# nrfusb.net
KiCad netlist of a schematic drawn in EAGLE
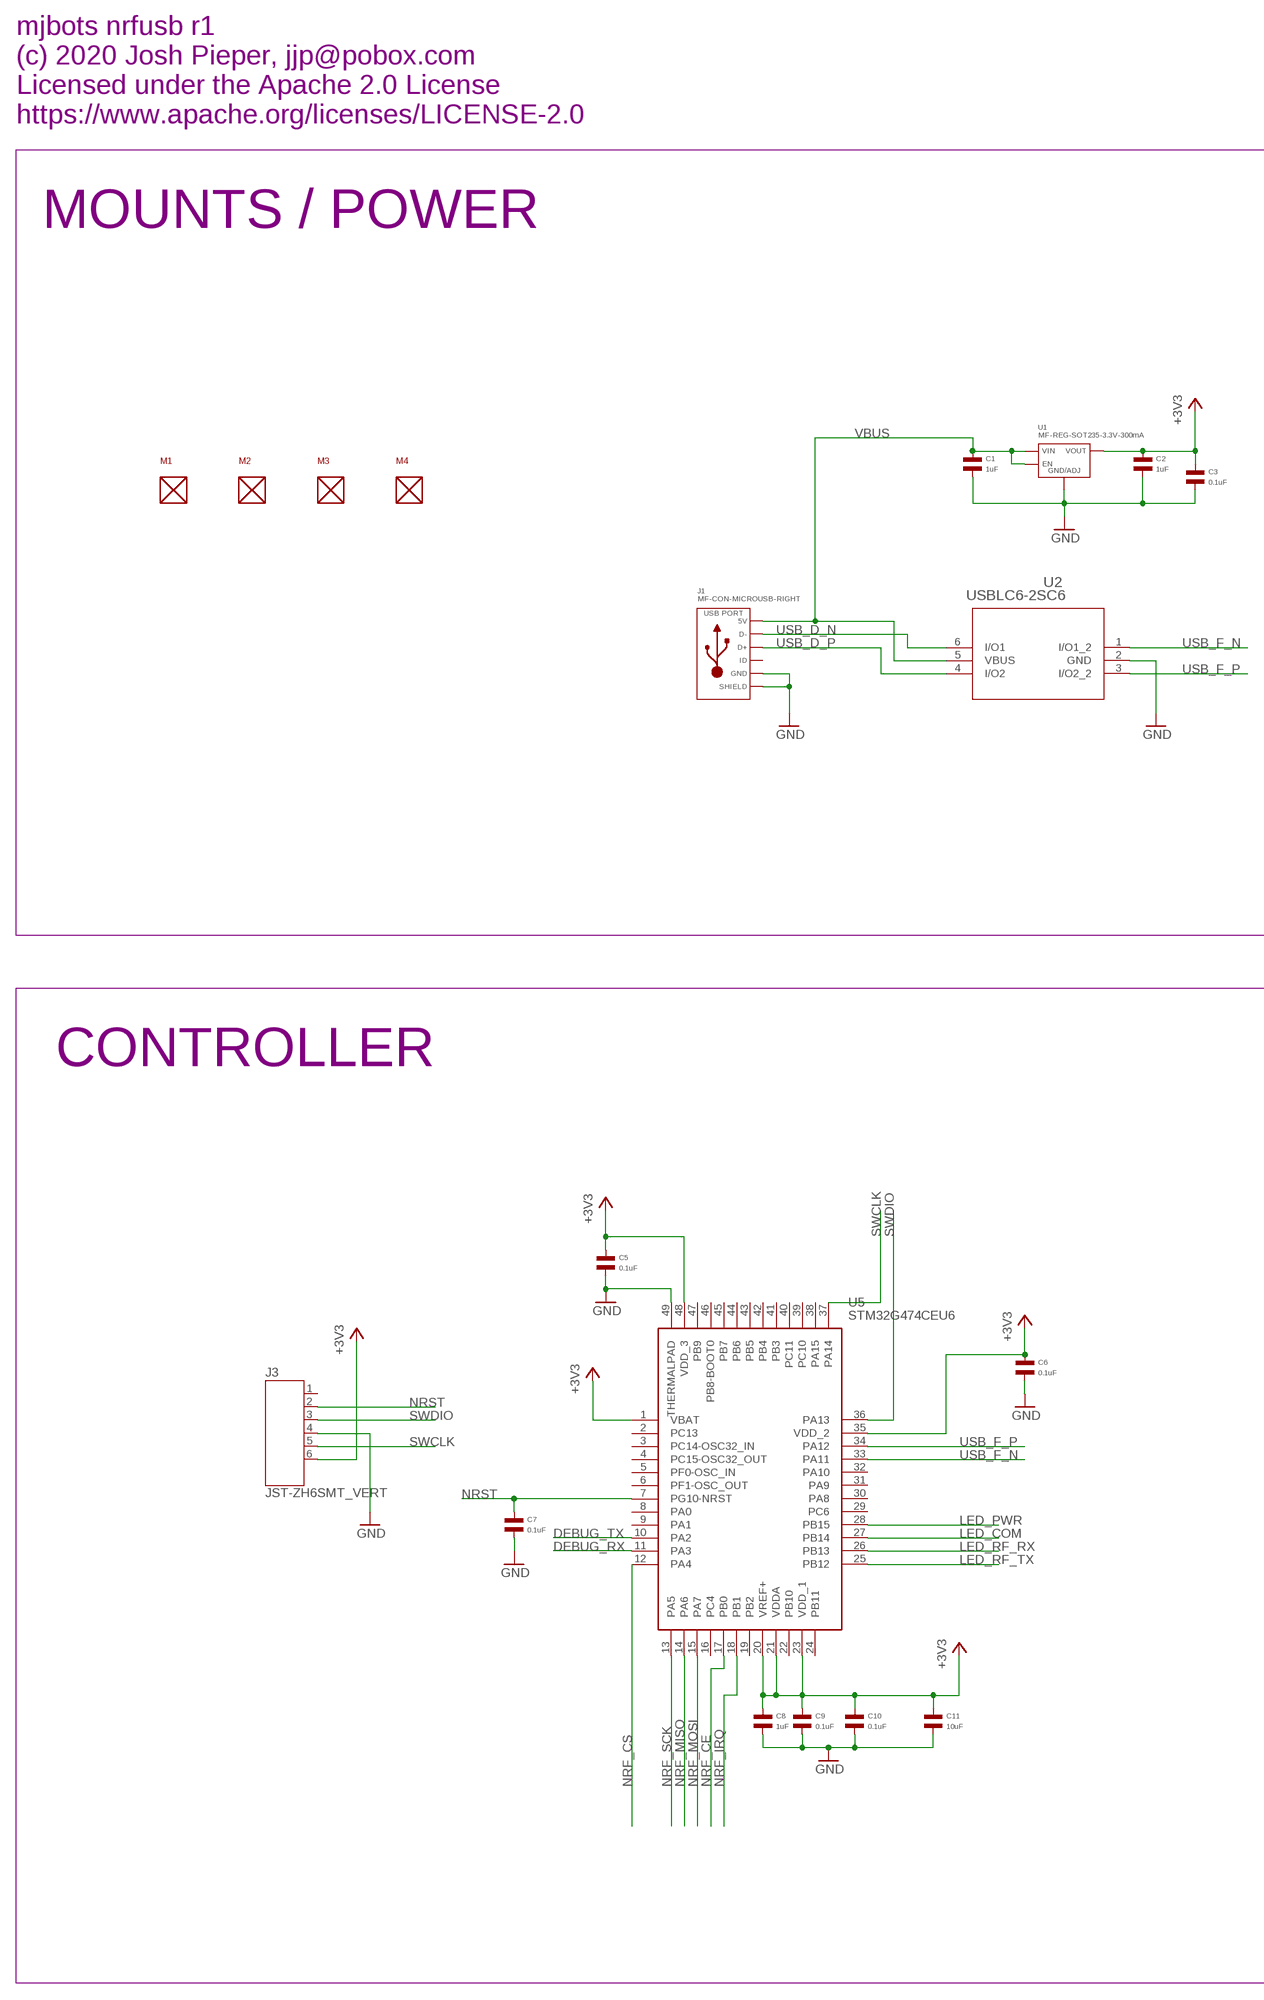
[diagram p0: schematic, sheet 1, part 1 of 2]
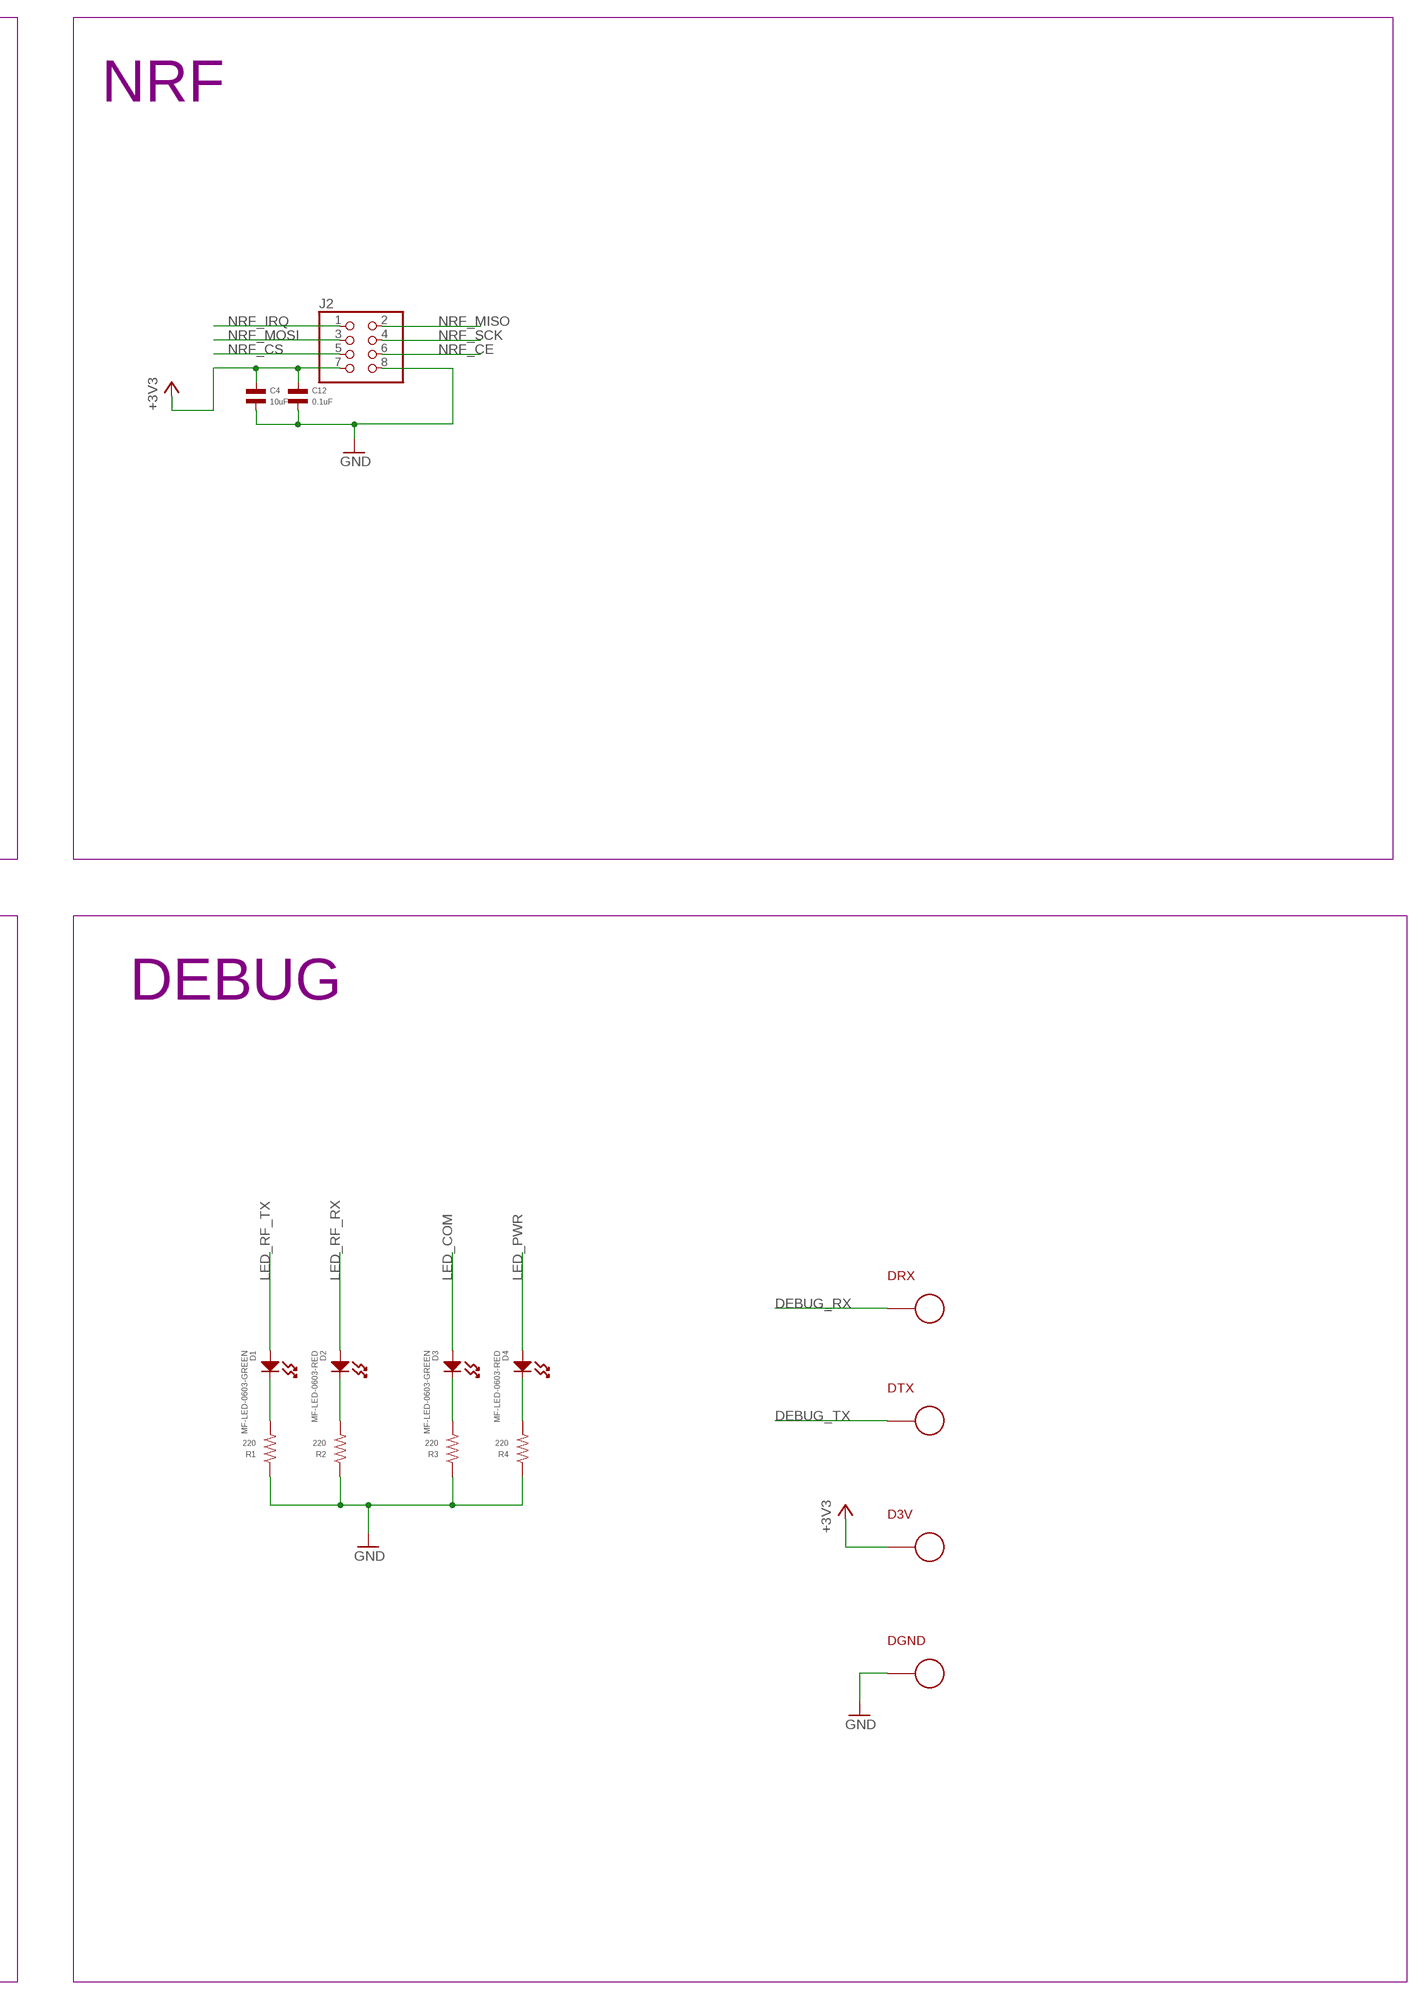
[diagram p1: schematic, sheet 1, part 2 of 2]

(export (version "E")
  (design (tool "Eeschema 10.0.6"))
  (components
    (comp (ref "C1")
      (value "1uF")
      (footprint "eagle-import:C0603")
      (fields (field (name "HOUSEPART") "YES") (field (name "MPN") "MF-CAP-0603-1uF"))
      (libsource (lib "eagle-import") (part "CAPACITOR_NP_0603"))
    )
    (comp (ref "C2")
      (value "1uF")
      (footprint "eagle-import:C0603")
      (fields (field (name "HOUSEPART") "YES") (field (name "MPN") "MF-CAP-0603-1uF"))
      (libsource (lib "eagle-import") (part "CAPACITOR_NP_0603"))
    )
    (comp (ref "C3")
      (value "0.1uF")
      (footprint "eagle-import:C0402")
      (fields (field (name "HOUSEPART") "YES") (field (name "MPN") "MF-CAP-0402-0.1uF"))
      (libsource (lib "eagle-import") (part "CAPACITOR_NP_0402"))
    )
    (comp (ref "C4")
      (value "10uF")
      (footprint "eagle-import:C1206")
      (fields (field (name "HOUSEPART") "YES") (field (name "MPN") "MF-CAP-1206-10uF"))
      (libsource (lib "eagle-import") (part "CAPACITOR_NP_1206"))
    )
    (comp (ref "C5")
      (value "0.1uF")
      (footprint "eagle-import:C0402")
      (fields (field (name "HOUSEPART") "YES") (field (name "MPN") "MF-CAP-0402-0.1uF"))
      (libsource (lib "eagle-import") (part "CAPACITOR_NP_0402"))
    )
    (comp (ref "C6")
      (value "0.1uF")
      (footprint "eagle-import:C0402")
      (fields (field (name "HOUSEPART") "YES") (field (name "MPN") "MF-CAP-0402-0.1uF"))
      (libsource (lib "eagle-import") (part "CAPACITOR_NP_0402"))
    )
    (comp (ref "C7")
      (value "0.1uF")
      (footprint "eagle-import:C0402")
      (fields (field (name "HOUSEPART") "YES") (field (name "MPN") "MF-CAP-0402-0.1uF"))
      (libsource (lib "eagle-import") (part "CAPACITOR_NP_0402"))
    )
    (comp (ref "C8")
      (value "1uF")
      (footprint "eagle-import:C0603")
      (fields (field (name "HOUSEPART") "YES") (field (name "MPN") "MF-CAP-0603-1uF"))
      (libsource (lib "eagle-import") (part "CAPACITOR_NP_0603"))
    )
    (comp (ref "C9")
      (value "0.1uF")
      (footprint "eagle-import:C0402")
      (fields (field (name "HOUSEPART") "YES") (field (name "MPN") "MF-CAP-0402-0.1uF"))
      (libsource (lib "eagle-import") (part "CAPACITOR_NP_0402"))
    )
    (comp (ref "C10")
      (value "0.1uF")
      (footprint "eagle-import:C0402")
      (fields (field (name "HOUSEPART") "YES") (field (name "MPN") "MF-CAP-0402-0.1uF"))
      (libsource (lib "eagle-import") (part "CAPACITOR_NP_0402"))
    )
    (comp (ref "C11")
      (value "10uF")
      (footprint "eagle-import:C1206")
      (fields (field (name "HOUSEPART") "YES") (field (name "MPN") "MF-CAP-1206-10uF"))
      (libsource (lib "eagle-import") (part "CAPACITOR_NP_1206"))
    )
    (comp (ref "C12")
      (value "0.1uF")
      (footprint "eagle-import:C0402")
      (fields (field (name "HOUSEPART") "YES") (field (name "MPN") "MF-CAP-0402-0.1uF"))
      (libsource (lib "eagle-import") (part "CAPACITOR_NP_0402"))
    )
    (comp (ref "D1")
      (value "MF-LED-0603-GREEN")
      (footprint "eagle-import:LED0603")
      (fields (field (name "HOUSEPART") "YES"))
      (libsource (lib "eagle-import") (part "LED_SINGLE-0603-GREEN"))
    )
    (comp (ref "D2")
      (value "MF-LED-0603-RED")
      (footprint "eagle-import:LED0603")
      (fields (field (name "HOUSEPART") "YES"))
      (libsource (lib "eagle-import") (part "LED_SINGLE-0603-RED"))
    )
    (comp (ref "D3")
      (value "MF-LED-0603-GREEN")
      (footprint "eagle-import:LED0603")
      (fields (field (name "HOUSEPART") "YES"))
      (libsource (lib "eagle-import") (part "LED_SINGLE-0603-GREEN"))
    )
    (comp (ref "D3V")
      (value "PAD24AWG_PAD")
      (footprint "eagle-import:24AWG_PAD")
      (libsource (lib "eagle-import") (part "PAD24AWG_PAD"))
    )
    (comp (ref "D4")
      (value "MF-LED-0603-RED")
      (footprint "eagle-import:LED0603")
      (fields (field (name "HOUSEPART") "YES"))
      (libsource (lib "eagle-import") (part "LED_SINGLE-0603-RED"))
    )
    (comp (ref "DGND")
      (value "PAD24AWG_PAD")
      (footprint "eagle-import:24AWG_PAD")
      (libsource (lib "eagle-import") (part "PAD24AWG_PAD"))
    )
    (comp (ref "DRX")
      (value "PAD24AWG_PAD")
      (footprint "eagle-import:24AWG_PAD")
      (libsource (lib "eagle-import") (part "PAD24AWG_PAD"))
    )
    (comp (ref "DTX")
      (value "PAD24AWG_PAD")
      (footprint "eagle-import:24AWG_PAD")
      (libsource (lib "eagle-import") (part "PAD24AWG_PAD"))
    )
    (comp (ref "J1")
      (value "MF-CON-MICROUSB-RIGHT")
      (footprint "eagle-import:MICROUSB-RIGHT")
      (fields (field (name "HOUSEPART") "YES"))
      (libsource (lib "eagle-import") (part "USB_MICRO_RIGHT"))
    )
    (comp (ref "J2")
      (value "PINHD-2X4")
      (footprint "eagle-import:2X04")
      (fields (field (name "MF") "WURTH") (field (name "MPN") "61300821121"))
      (libsource (lib "eagle-import") (part "PINHD-2X4"))
    )
    (comp (ref "J3")
      (value "JST-ZH6SMT_VERT")
      (footprint "eagle-import:JST_B6B-ZR-SM4-TF(LF)(SN)")
      (fields (field (name "MF") "JST") (field (name "MPN") "B6B-ZR-SM4-TF(LF)(SN)"))
      (libsource (lib "eagle-import") (part "JST-ZH6SMT_VERT"))
    )
    (comp (ref "M1")
      (value "MOUNT")
      (footprint "eagle-import:M2.5MOUNT")
      (libsource (lib "eagle-import") (part "MOUNT"))
    )
    (comp (ref "M2")
      (value "MOUNT")
      (footprint "eagle-import:M2.5MOUNT")
      (libsource (lib "eagle-import") (part "MOUNT"))
    )
    (comp (ref "M3")
      (value "MOUNT")
      (footprint "eagle-import:M2.5MOUNT")
      (libsource (lib "eagle-import") (part "MOUNT"))
    )
    (comp (ref "M4")
      (value "MOUNT")
      (footprint "eagle-import:M2.5MOUNT")
      (libsource (lib "eagle-import") (part "MOUNT"))
    )
    (comp (ref "R1")
      (value "220")
      (footprint "eagle-import:R0402")
      (fields (field (name "MPN") "MF-RES-0402-220"))
      (libsource (lib "eagle-import") (part "RESISTOR_0402"))
    )
    (comp (ref "R2")
      (value "220")
      (footprint "eagle-import:R0402")
      (fields (field (name "MPN") "MF-RES-0402-220"))
      (libsource (lib "eagle-import") (part "RESISTOR_0402"))
    )
    (comp (ref "R3")
      (value "220")
      (footprint "eagle-import:R0402")
      (fields (field (name "MPN") "MF-RES-0402-220"))
      (libsource (lib "eagle-import") (part "RESISTOR_0402"))
    )
    (comp (ref "R4")
      (value "220")
      (footprint "eagle-import:R0402")
      (fields (field (name "MPN") "MF-RES-0402-220"))
      (libsource (lib "eagle-import") (part "RESISTOR_0402"))
    )
    (comp (ref "U1")
      (value "MF-REG-SOT235-3.3V-300mA")
      (footprint "eagle-import:SOT-23-5")
      (fields (field (name "HOUSEPART") "YES"))
      (libsource (lib "eagle-import") (part "TLV70233PDBVR"))
    )
    (comp (ref "U2")
      (value "USBLC6-2SC6")
      (footprint "eagle-import:SOT23-6L")
      (fields (field (name "MANUFACTURER_PART_NUMBER") "USBLC62SC6") (field (name "MF") "ST"))
      (libsource (lib "eagle-import") (part "USBLC6-2SC6"))
    )
    (comp (ref "U5")
      (value "STM32G474CEU6")
      (footprint "eagle-import:QFN50P700X700X60-49N")
      (fields (field (name "MOUSER_PART_NUMBER") "511-STM32G474CEU6") (field (name "MF") "ST"))
      (libsource (lib "eagle-import") (part "STM32G474CEU6"))
    )
  )
  (nets
    (net (code "1") (name "+3V3") (class "Default")
      (node (ref "C10") (pin "P$1") (pinfunction "P$1_P$1") (pintype "passive"))
      (node (ref "C11") (pin "P$1") (pinfunction "P$1_P$1") (pintype "passive"))
      (node (ref "C12") (pin "P$1") (pinfunction "P$1_P$1") (pintype "passive"))
      (node (ref "C2") (pin "P$1") (pinfunction "P$1_P$1") (pintype "passive"))
      (node (ref "C3") (pin "P$1") (pinfunction "P$1_P$1") (pintype "passive"))
      (node (ref "C4") (pin "P$1") (pinfunction "P$1_P$1") (pintype "passive"))
      (node (ref "C5") (pin "P$1") (pinfunction "P$1_P$1") (pintype "passive"))
      (node (ref "C6") (pin "P$1") (pinfunction "P$1_P$1") (pintype "passive"))
      (node (ref "C8") (pin "P$1") (pinfunction "P$1_P$1") (pintype "passive"))
      (node (ref "C9") (pin "P$1") (pinfunction "P$1_P$1") (pintype "passive"))
      (node (ref "D3V") (pin "P$1") (pinfunction "P$1_P$1") (pintype "bidirectional"))
      (node (ref "J2") (pin "7") (pinfunction "7_7") (pintype "passive"))
      (node (ref "J3") (pin "6") (pinfunction "6_6") (pintype "passive"))
      (node (ref "U1") (pin "P$5") (pinfunction "VOUT_P$5") (pintype "bidirectional"))
      (node (ref "U5") (pin "1") (pinfunction "VBAT_1") (pintype "bidirectional"))
      (node (ref "U5") (pin "20") (pinfunction "VREF+_20") (pintype "bidirectional"))
      (node (ref "U5") (pin "21") (pinfunction "VDDA_21") (pintype "bidirectional"))
      (node (ref "U5") (pin "23") (pinfunction "VDD_1_23") (pintype "bidirectional"))
      (node (ref "U5") (pin "35") (pinfunction "VDD_2_35") (pintype "bidirectional"))
      (node (ref "U5") (pin "48") (pinfunction "VDD_3_48") (pintype "bidirectional"))
    )
    (net (code "2") (name "/DEBUG_RX") (class "Default")
      (node (ref "DRX") (pin "P$1") (pinfunction "P$1_P$1") (pintype "bidirectional"))
      (node (ref "U5") (pin "11") (pinfunction "PA3_11") (pintype "bidirectional"))
    )
    (net (code "3") (name "/DEBUG_TX") (class "Default")
      (node (ref "DTX") (pin "P$1") (pinfunction "P$1_P$1") (pintype "bidirectional"))
      (node (ref "U5") (pin "10") (pinfunction "PA2_10") (pintype "bidirectional"))
    )
    (net (code "4") (name "/LED_COM") (class "Default")
      (node (ref "D3") (pin "ANODE") (pinfunction "ANODE_ANODE") (pintype "power_in"))
      (node (ref "U5") (pin "27") (pinfunction "PB14_27") (pintype "bidirectional"))
    )
    (net (code "5") (name "/LED_PWR") (class "Default")
      (node (ref "D4") (pin "ANODE") (pinfunction "ANODE_ANODE") (pintype "power_in"))
      (node (ref "U5") (pin "28") (pinfunction "PB15_28") (pintype "bidirectional"))
    )
    (net (code "6") (name "/LED_RF_RX") (class "Default")
      (node (ref "D2") (pin "ANODE") (pinfunction "ANODE_ANODE") (pintype "power_in"))
      (node (ref "U5") (pin "26") (pinfunction "PB13_26") (pintype "bidirectional"))
    )
    (net (code "7") (name "/LED_RF_TX") (class "Default")
      (node (ref "D1") (pin "ANODE") (pinfunction "ANODE_ANODE") (pintype "power_in"))
      (node (ref "U5") (pin "25") (pinfunction "PB12_25") (pintype "bidirectional"))
    )
    (net (code "8") (name "/NRF_CE") (class "Default")
      (node (ref "J2") (pin "6") (pinfunction "6_6") (pintype "passive"))
      (node (ref "U5") (pin "17") (pinfunction "PB0_17") (pintype "bidirectional"))
    )
    (net (code "9") (name "/NRF_CS") (class "Default")
      (node (ref "J2") (pin "5") (pinfunction "5_5") (pintype "passive"))
      (node (ref "U5") (pin "12") (pinfunction "PA4_12") (pintype "bidirectional"))
    )
    (net (code "10") (name "/NRF_IRQ") (class "Default")
      (node (ref "J2") (pin "1") (pinfunction "1_1") (pintype "passive"))
      (node (ref "U5") (pin "18") (pinfunction "PB1_18") (pintype "bidirectional"))
    )
    (net (code "11") (name "/NRF_MISO") (class "Default")
      (node (ref "J2") (pin "2") (pinfunction "2_2") (pintype "passive"))
      (node (ref "U5") (pin "14") (pinfunction "PA6_14") (pintype "bidirectional"))
    )
    (net (code "12") (name "/NRF_MOSI") (class "Default")
      (node (ref "J2") (pin "3") (pinfunction "3_3") (pintype "passive"))
      (node (ref "U5") (pin "15") (pinfunction "PA7_15") (pintype "bidirectional"))
    )
    (net (code "13") (name "/NRF_SCK") (class "Default")
      (node (ref "J2") (pin "4") (pinfunction "4_4") (pintype "passive"))
      (node (ref "U5") (pin "13") (pinfunction "PA5_13") (pintype "bidirectional"))
    )
    (net (code "14") (name "/NRST") (class "Default")
      (node (ref "C7") (pin "P$1") (pinfunction "P$1_P$1") (pintype "passive"))
      (node (ref "J3") (pin "2") (pinfunction "2_2") (pintype "passive"))
      (node (ref "U5") (pin "7") (pinfunction "PG10-NRST_7") (pintype "bidirectional"))
    )
    (net (code "15") (name "/SWCLK") (class "Default")
      (node (ref "J3") (pin "5") (pinfunction "5_5") (pintype "passive"))
      (node (ref "U5") (pin "37") (pinfunction "PA14_37") (pintype "bidirectional"))
    )
    (net (code "16") (name "/SWDIO") (class "Default")
      (node (ref "J3") (pin "3") (pinfunction "3_3") (pintype "passive"))
      (node (ref "U5") (pin "36") (pinfunction "PA13_36") (pintype "bidirectional"))
    )
    (net (code "17") (name "/USB_D_N") (class "Default")
      (node (ref "J1") (pin "2") (pinfunction "D-_2") (pintype "bidirectional"))
      (node (ref "U2") (pin "6") (pinfunction "I/O1_6") (pintype "bidirectional"))
    )
    (net (code "18") (name "/USB_D_P") (class "Default")
      (node (ref "J1") (pin "3") (pinfunction "D+_3") (pintype "bidirectional"))
      (node (ref "U2") (pin "4") (pinfunction "I/O2_4") (pintype "bidirectional"))
    )
    (net (code "19") (name "/USB_F_N") (class "Default")
      (node (ref "U2") (pin "1") (pinfunction "I/O1_2_1") (pintype "bidirectional"))
      (node (ref "U5") (pin "33") (pinfunction "PA11_33") (pintype "bidirectional"))
    )
    (net (code "20") (name "/USB_F_P") (class "Default")
      (node (ref "U2") (pin "3") (pinfunction "I/O2_2_3") (pintype "bidirectional"))
      (node (ref "U5") (pin "34") (pinfunction "PA12_34") (pintype "bidirectional"))
    )
    (net (code "21") (name "/VBUS") (class "Default")
      (node (ref "C1") (pin "P$1") (pinfunction "P$1_P$1") (pintype "passive"))
      (node (ref "J1") (pin "1") (pinfunction "5V_1") (pintype "power_in"))
      (node (ref "U1") (pin "P$1") (pinfunction "VIN_P$1") (pintype "bidirectional"))
      (node (ref "U1") (pin "P$3") (pinfunction "EN_P$3") (pintype "bidirectional"))
      (node (ref "U2") (pin "5") (pinfunction "VBUS_5") (pintype "power_in"))
    )
    (net (code "22") (name "GND") (class "Default")
      (node (ref "C1") (pin "P$2") (pinfunction "P$2_P$2") (pintype "passive"))
      (node (ref "C10") (pin "P$2") (pinfunction "P$2_P$2") (pintype "passive"))
      (node (ref "C11") (pin "P$2") (pinfunction "P$2_P$2") (pintype "passive"))
      (node (ref "C12") (pin "P$2") (pinfunction "P$2_P$2") (pintype "passive"))
      (node (ref "C2") (pin "P$2") (pinfunction "P$2_P$2") (pintype "passive"))
      (node (ref "C3") (pin "P$2") (pinfunction "P$2_P$2") (pintype "passive"))
      (node (ref "C4") (pin "P$2") (pinfunction "P$2_P$2") (pintype "passive"))
      (node (ref "C5") (pin "P$2") (pinfunction "P$2_P$2") (pintype "passive"))
      (node (ref "C6") (pin "P$2") (pinfunction "P$2_P$2") (pintype "passive"))
      (node (ref "C7") (pin "P$2") (pinfunction "P$2_P$2") (pintype "passive"))
      (node (ref "C8") (pin "P$2") (pinfunction "P$2_P$2") (pintype "passive"))
      (node (ref "C9") (pin "P$2") (pinfunction "P$2_P$2") (pintype "passive"))
      (node (ref "DGND") (pin "P$1") (pinfunction "P$1_P$1") (pintype "bidirectional"))
      (node (ref "J1") (pin "5") (pinfunction "GND_5") (pintype "power_in"))
      (node (ref "J1") (pin "S1") (pinfunction "SLD_S1") (pintype "power_in"))
      (node (ref "J1") (pin "S2") (pinfunction "SLD_S2") (pintype "power_in"))
      (node (ref "J1") (pin "S3") (pinfunction "SLD_S3") (pintype "power_in"))
      (node (ref "J1") (pin "S4") (pinfunction "SLD_S4") (pintype "power_in"))
      (node (ref "J1") (pin "S5") (pinfunction "SLD_S5") (pintype "power_in"))
      (node (ref "J1") (pin "S6") (pinfunction "SLD_S6") (pintype "power_in"))
      (node (ref "J2") (pin "8") (pinfunction "8_8") (pintype "passive"))
      (node (ref "J3") (pin "4") (pinfunction "4_4") (pintype "passive"))
      (node (ref "R1") (pin "P$1") (pinfunction "P$1_P$1") (pintype "passive"))
      (node (ref "R2") (pin "P$1") (pinfunction "P$1_P$1") (pintype "passive"))
      (node (ref "R3") (pin "P$1") (pinfunction "P$1_P$1") (pintype "passive"))
      (node (ref "R4") (pin "P$1") (pinfunction "P$1_P$1") (pintype "passive"))
      (node (ref "U1") (pin "P$2") (pinfunction "GND/ADJ_P$2") (pintype "bidirectional"))
      (node (ref "U2") (pin "2") (pinfunction "GND_2") (pintype "power_in"))
      (node (ref "U5") (pin "49") (pinfunction "THERMALPAD_49") (pintype "bidirectional"))
    )
    (net (code "23") (name "Net-(D1-PadCATHODE)") (class "Default")
      (node (ref "D1") (pin "CATHODE") (pinfunction "CATHODE_CATHODE") (pintype "power_in"))
      (node (ref "R1") (pin "P$2") (pinfunction "P$2_P$2") (pintype "passive"))
    )
    (net (code "24") (name "Net-(D2-PadCATHODE)") (class "Default")
      (node (ref "D2") (pin "CATHODE") (pinfunction "CATHODE_CATHODE") (pintype "power_in"))
      (node (ref "R2") (pin "P$2") (pinfunction "P$2_P$2") (pintype "passive"))
    )
    (net (code "25") (name "Net-(D3-PadCATHODE)") (class "Default")
      (node (ref "D3") (pin "CATHODE") (pinfunction "CATHODE_CATHODE") (pintype "power_in"))
      (node (ref "R3") (pin "P$2") (pinfunction "P$2_P$2") (pintype "passive"))
    )
    (net (code "26") (name "Net-(D4-PadCATHODE)") (class "Default")
      (node (ref "D4") (pin "CATHODE") (pinfunction "CATHODE_CATHODE") (pintype "power_in"))
      (node (ref "R4") (pin "P$2") (pinfunction "P$2_P$2") (pintype "passive"))
    )
    (net (code "27") (name "unconnected-(J1-ID-Pad4)") (class "Default")
      (node (ref "J1") (pin "4") (pinfunction "ID_4") (pintype "bidirectional"))
    )
    (net (code "28") (name "unconnected-(J3-Pad1)") (class "Default")
      (node (ref "J3") (pin "1") (pinfunction "1_1") (pintype "passive"))
    )
    (net (code "29") (name "unconnected-(U5-PA0-Pad8)") (class "Default")
      (node (ref "U5") (pin "8") (pinfunction "PA0_8") (pintype "bidirectional"))
    )
    (net (code "30") (name "unconnected-(U5-PA1-Pad9)") (class "Default")
      (node (ref "U5") (pin "9") (pinfunction "PA1_9") (pintype "bidirectional"))
    )
    (net (code "31") (name "unconnected-(U5-PA8-Pad30)") (class "Default")
      (node (ref "U5") (pin "30") (pinfunction "PA8_30") (pintype "bidirectional"))
    )
    (net (code "32") (name "unconnected-(U5-PA9-Pad31)") (class "Default")
      (node (ref "U5") (pin "31") (pinfunction "PA9_31") (pintype "bidirectional"))
    )
    (net (code "33") (name "unconnected-(U5-PA10-Pad32)") (class "Default")
      (node (ref "U5") (pin "32") (pinfunction "PA10_32") (pintype "bidirectional"))
    )
    (net (code "34") (name "unconnected-(U5-PA15-Pad38)") (class "Default")
      (node (ref "U5") (pin "38") (pinfunction "PA15_38") (pintype "bidirectional"))
    )
    (net (code "35") (name "unconnected-(U5-PB2-Pad19)") (class "Default")
      (node (ref "U5") (pin "19") (pinfunction "PB2_19") (pintype "bidirectional"))
    )
    (net (code "36") (name "unconnected-(U5-PB3-Pad41)") (class "Default")
      (node (ref "U5") (pin "41") (pinfunction "PB3_41") (pintype "bidirectional"))
    )
    (net (code "37") (name "unconnected-(U5-PB4-Pad42)") (class "Default")
      (node (ref "U5") (pin "42") (pinfunction "PB4_42") (pintype "bidirectional"))
    )
    (net (code "38") (name "unconnected-(U5-PB5-Pad43)") (class "Default")
      (node (ref "U5") (pin "43") (pinfunction "PB5_43") (pintype "bidirectional"))
    )
    (net (code "39") (name "unconnected-(U5-PB6-Pad44)") (class "Default")
      (node (ref "U5") (pin "44") (pinfunction "PB6_44") (pintype "bidirectional"))
    )
    (net (code "40") (name "unconnected-(U5-PB7-Pad45)") (class "Default")
      (node (ref "U5") (pin "45") (pinfunction "PB7_45") (pintype "bidirectional"))
    )
    (net (code "41") (name "unconnected-(U5-PB8-BOOT0-Pad46)") (class "Default")
      (node (ref "U5") (pin "46") (pinfunction "PB8-BOOT0_46") (pintype "bidirectional"))
    )
    (net (code "42") (name "unconnected-(U5-PB9-Pad47)") (class "Default")
      (node (ref "U5") (pin "47") (pinfunction "PB9_47") (pintype "bidirectional"))
    )
    (net (code "43") (name "unconnected-(U5-PB10-Pad22)") (class "Default")
      (node (ref "U5") (pin "22") (pinfunction "PB10_22") (pintype "bidirectional"))
    )
    (net (code "44") (name "unconnected-(U5-PB11-Pad24)") (class "Default")
      (node (ref "U5") (pin "24") (pinfunction "PB11_24") (pintype "bidirectional"))
    )
    (net (code "45") (name "unconnected-(U5-PC4-Pad16)") (class "Default")
      (node (ref "U5") (pin "16") (pinfunction "PC4_16") (pintype "bidirectional"))
    )
    (net (code "46") (name "unconnected-(U5-PC6-Pad29)") (class "Default")
      (node (ref "U5") (pin "29") (pinfunction "PC6_29") (pintype "bidirectional"))
    )
    (net (code "47") (name "unconnected-(U5-PC10-Pad39)") (class "Default")
      (node (ref "U5") (pin "39") (pinfunction "PC10_39") (pintype "bidirectional"))
    )
    (net (code "48") (name "unconnected-(U5-PC11-Pad40)") (class "Default")
      (node (ref "U5") (pin "40") (pinfunction "PC11_40") (pintype "bidirectional"))
    )
    (net (code "49") (name "unconnected-(U5-PC13-Pad2)") (class "Default")
      (node (ref "U5") (pin "2") (pinfunction "PC13_2") (pintype "bidirectional"))
    )
    (net (code "50") (name "unconnected-(U5-PC14-OSC32_IN-Pad3)") (class "Default")
      (node (ref "U5") (pin "3") (pinfunction "PC14-OSC32_IN_3") (pintype "bidirectional"))
    )
    (net (code "51") (name "unconnected-(U5-PC15-OSC32_OUT-Pad4)") (class "Default")
      (node (ref "U5") (pin "4") (pinfunction "PC15-OSC32_OUT_4") (pintype "bidirectional"))
    )
    (net (code "52") (name "unconnected-(U5-PF0-OSC_IN-Pad5)") (class "Default")
      (node (ref "U5") (pin "5") (pinfunction "PF0-OSC_IN_5") (pintype "bidirectional"))
    )
    (net (code "53") (name "unconnected-(U5-PF1-OSC_OUT-Pad6)") (class "Default")
      (node (ref "U5") (pin "6") (pinfunction "PF1-OSC_OUT_6") (pintype "bidirectional"))
    )
  )
)
